# power.net
KiCad netlist of a schematic drawn in Altium Designer
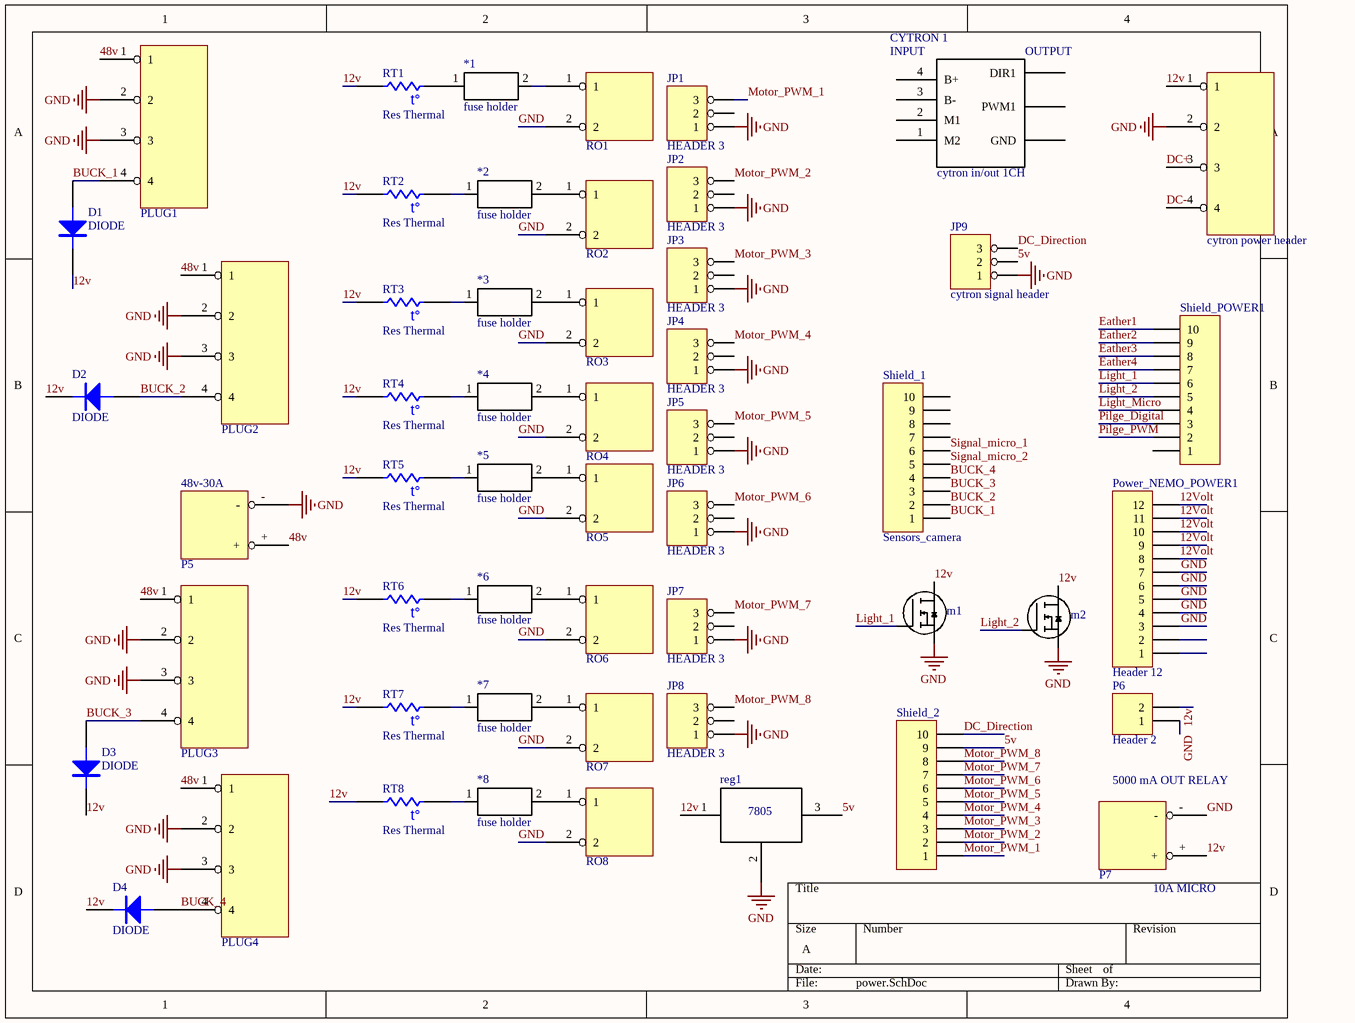
[diagram p0: power.SchDoc]

(export (version "E")
  (design (tool "Eeschema 10.0.6"))
  (components
    (comp (ref "*1")
      (value "fuse holder")
      (footprint "fuse Holder")
      (libsource (lib "RELAY 5V") (part "fuse holder"))
    )
    (comp (ref "*2")
      (value "fuse holder")
      (footprint "fuse Holder")
      (libsource (lib "RELAY 5V") (part "fuse holder"))
    )
    (comp (ref "*3")
      (value "fuse holder")
      (footprint "fuse Holder")
      (libsource (lib "RELAY 5V") (part "fuse holder"))
    )
    (comp (ref "*4")
      (value "fuse holder")
      (footprint "fuse Holder")
      (libsource (lib "RELAY 5V") (part "fuse holder"))
    )
    (comp (ref "*5")
      (value "fuse holder")
      (footprint "fuse Holder")
      (libsource (lib "RELAY 5V") (part "fuse holder"))
    )
    (comp (ref "*6")
      (value "fuse holder")
      (footprint "fuse Holder")
      (libsource (lib "RELAY 5V") (part "fuse holder"))
    )
    (comp (ref "*7")
      (value "fuse holder")
      (footprint "fuse Holder")
      (libsource (lib "RELAY 5V") (part "fuse holder"))
    )
    (comp (ref "*8")
      (value "fuse holder")
      (footprint "fuse Holder")
      (libsource (lib "RELAY 5V") (part "fuse holder"))
    )
    (comp (ref "CYTRON 1")
      (value "cytron in/out 1CH")
      (footprint "cytron in/out 1CH")
      (libsource (lib "RELAY 5V") (part "cytron in/out 1CH"))
    )
    (comp (ref "cytron power header")
      (value "Rossetta 4-pin")
      (footprint "Rossetta 4-pin plugable")
      (fields (field (name "CREATED BY") "NourAldin"))
      (libsource (lib "crocomarine") (part "Rossetta 4-pin"))
    )
    (comp (ref "D1")
      (value "DIODE")
      (footprint "AXIAL0.3")
      (description "Diode")
      (libsource (lib "Final Library") (part "DIODE"))
    )
    (comp (ref "D2")
      (value "DIODE")
      (footprint "AXIAL0.3")
      (description "Diode")
      (libsource (lib "Final Library") (part "DIODE"))
    )
    (comp (ref "D3")
      (value "DIODE")
      (footprint "AXIAL0.3")
      (description "Diode")
      (libsource (lib "Final Library") (part "DIODE"))
    )
    (comp (ref "D4")
      (value "DIODE")
      (footprint "AXIAL0.3")
      (description "Diode")
      (libsource (lib "Final Library") (part "DIODE"))
    )
    (comp (ref "JP1")
      (value "HEADER 3")
      (footprint "SIP3")
      (libsource (lib "Final Library") (part "HEADER 3"))
    )
    (comp (ref "JP2")
      (value "HEADER 3")
      (footprint "SIP3")
      (libsource (lib "Final Library") (part "HEADER 3"))
    )
    (comp (ref "JP3")
      (value "HEADER 3")
      (footprint "SIP3")
      (libsource (lib "Final Library") (part "HEADER 3"))
    )
    (comp (ref "JP4")
      (value "HEADER 3")
      (footprint "SIP3")
      (libsource (lib "Final Library") (part "HEADER 3"))
    )
    (comp (ref "JP5")
      (value "HEADER 3")
      (footprint "SIP3")
      (libsource (lib "Final Library") (part "HEADER 3"))
    )
    (comp (ref "JP6")
      (value "HEADER 3")
      (footprint "SIP3")
      (libsource (lib "Final Library") (part "HEADER 3"))
    )
    (comp (ref "JP7")
      (value "HEADER 3")
      (footprint "SIP3")
      (libsource (lib "Final Library") (part "HEADER 3"))
    )
    (comp (ref "JP8")
      (value "HEADER 3")
      (footprint "SIP3")
      (libsource (lib "Final Library") (part "HEADER 3"))
    )
    (comp (ref "JP9")
      (value "cytron signal header")
      (footprint "SIP3")
      (libsource (lib "Final Library") (part "HEADER 3"))
    )
    (comp (ref "m1")
      (value "MOSFET")
      (footprint "TO252")
      (libsource (lib "sig_lib") (part "MOSFET   AP9997AGH"))
    )
    (comp (ref "m2")
      (value "MOSFET")
      (footprint "TO252")
      (libsource (lib "sig_lib") (part "MOSFET   AP9997AGH"))
    )
    (comp (ref "P5")
      (value "48v-30A")
      (footprint "XT-60")
      (description "XT-60 Connector")
      (libsource (lib "crocomarine (1)") (part "XT-60"))
    )
    (comp (ref "P6")
      (value "Header 2")
      (footprint "HDR1X2")
      (description "Header, 2-Pin")
      (fields (field (name "PUBLISHER") "Altium Limited"))
      (libsource (lib "Miscellaneous Connectors") (part "Header 2"))
    )
    (comp (ref "P7")
      (value "XT-60")
      (footprint "XT-60")
      (description "XT-60 Connector")
      (libsource (lib "crocomarine (1)") (part "XT-60"))
    )
    (comp (ref "PLUG1")
      (value "Rossetta 4-pin")
      (footprint "Rossetta 4-pin plugable")
      (fields (field (name "CREATED BY") "NourAldin"))
      (libsource (lib "crocomarine") (part "Rossetta 4-pin"))
    )
    (comp (ref "PLUG2")
      (value "Rossetta 4-pin")
      (footprint "Rossetta 4-pin plugable")
      (fields (field (name "CREATED BY") "NourAldin"))
      (libsource (lib "crocomarine") (part "Rossetta 4-pin"))
    )
    (comp (ref "PLUG3")
      (value "Rossetta 4-pin")
      (footprint "Rossetta 4-pin plugable")
      (fields (field (name "CREATED BY") "NourAldin"))
      (libsource (lib "crocomarine") (part "Rossetta 4-pin"))
    )
    (comp (ref "PLUG4")
      (value "Rossetta 4-pin")
      (footprint "Rossetta 4-pin plugable")
      (fields (field (name "CREATED BY") "NourAldin"))
      (libsource (lib "crocomarine") (part "Rossetta 4-pin"))
    )
    (comp (ref "Power_NEMO_POWER1")
      (value "Header 12")
      (footprint "HDR1X12")
      (description "Header, 12-Pin")
      (fields (field (name "PUBLISHER") "Altium Limited"))
      (libsource (lib "Miscellaneous Connectors") (part "Header 12"))
    )
    (comp (ref "reg1") (value "7805") (footprint "7805") (libsource (lib "RELAY") (part "7805")))
    (comp (ref "RO1")
      (value "Rossetta")
      (footprint "Rossetta 2-pin")
      (libsource (lib "crocomarine") (part "Rossetta"))
    )
    (comp (ref "RO2")
      (value "Rossetta")
      (footprint "Rossetta 2-pin")
      (libsource (lib "crocomarine") (part "Rossetta"))
    )
    (comp (ref "RO3")
      (value "Rossetta")
      (footprint "Rossetta 2-pin")
      (libsource (lib "crocomarine") (part "Rossetta"))
    )
    (comp (ref "RO4")
      (value "Rossetta")
      (footprint "Rossetta 2-pin")
      (libsource (lib "crocomarine") (part "Rossetta"))
    )
    (comp (ref "RO5")
      (value "Rossetta")
      (footprint "Rossetta 2-pin")
      (libsource (lib "crocomarine") (part "Rossetta"))
    )
    (comp (ref "RO6")
      (value "Rossetta")
      (footprint "Rossetta 2-pin")
      (libsource (lib "crocomarine") (part "Rossetta"))
    )
    (comp (ref "RO7")
      (value "Rossetta")
      (footprint "Rossetta 2-pin")
      (libsource (lib "crocomarine") (part "Rossetta"))
    )
    (comp (ref "RO8")
      (value "Rossetta")
      (footprint "Rossetta 2-pin")
      (libsource (lib "crocomarine") (part "Rossetta"))
    )
    (comp (ref "RT1")
      (value "Res Thermal")
      (footprint "6-0805_N")
      (description "Thermistor")
      (fields (field (name "PUBLISHER") "Altium Limited"))
      (libsource (lib "Miscellaneous Devices") (part "Res Thermal"))
    )
    (comp (ref "RT2")
      (value "Res Thermal")
      (footprint "6-0805_N")
      (description "Thermistor")
      (fields (field (name "PUBLISHER") "Altium Limited"))
      (libsource (lib "Miscellaneous Devices") (part "Res Thermal"))
    )
    (comp (ref "RT3")
      (value "Res Thermal")
      (footprint "6-0805_N")
      (description "Thermistor")
      (fields (field (name "PUBLISHER") "Altium Limited"))
      (libsource (lib "Miscellaneous Devices") (part "Res Thermal"))
    )
    (comp (ref "RT4")
      (value "Res Thermal")
      (footprint "6-0805_N")
      (description "Thermistor")
      (fields (field (name "PUBLISHER") "Altium Limited"))
      (libsource (lib "Miscellaneous Devices") (part "Res Thermal"))
    )
    (comp (ref "RT5")
      (value "Res Thermal")
      (footprint "6-0805_N")
      (description "Thermistor")
      (fields (field (name "PUBLISHER") "Altium Limited"))
      (libsource (lib "Miscellaneous Devices") (part "Res Thermal"))
    )
    (comp (ref "RT6")
      (value "Res Thermal")
      (footprint "6-0805_N")
      (description "Thermistor")
      (fields (field (name "PUBLISHER") "Altium Limited"))
      (libsource (lib "Miscellaneous Devices") (part "Res Thermal"))
    )
    (comp (ref "RT7")
      (value "Res Thermal")
      (footprint "6-0805_N")
      (description "Thermistor")
      (fields (field (name "PUBLISHER") "Altium Limited"))
      (libsource (lib "Miscellaneous Devices") (part "Res Thermal"))
    )
    (comp (ref "RT8")
      (value "Res Thermal")
      (footprint "6-0805_N")
      (description "Thermistor")
      (fields (field (name "PUBLISHER") "Altium Limited"))
      (libsource (lib "Miscellaneous Devices") (part "Res Thermal"))
    )
    (comp (ref "Shield_1")
      (value "Sensors_camera")
      (footprint "HDR1X10")
      (description "Header, 10-Pin")
      (fields (field (name "PUBLISHER") "Altium Limited"))
      (libsource (lib "") (part "Header 10_1"))
    )
    (comp (ref "Shield_2")
      (value "Header 10")
      (footprint "HDR1X10")
      (description "Header, 10-Pin")
      (fields (field (name "PUBLISHER") "Altium Limited"))
      (libsource (lib "") (part "Header 10_1"))
    )
    (comp (ref "Shield_POWER1")
      (value "Header 10")
      (footprint "HDR1X10")
      (description "Header, 10-Pin")
      (fields (field (name "PUBLISHER") "Altium Limited"))
      (libsource (lib "Miscellaneous Connectors") (part "Header 10"))
    )
  )
  (nets
    (net (code "1") (name "/5v") (class "Default")
      (node (ref "JP9") (pin "2") (pinfunction "2_2") (pintype "passive"))
      (node (ref "Shield_2") (pin "9") (pinfunction "9_9") (pintype "passive"))
      (node (ref "reg1") (pin "3") (pinfunction "v_out_3") (pintype "passive"))
    )
    (net (code "2") (name "/12Volt") (class "Default")
      (node (ref "Power_NEMO_POWER1") (pin "10") (pinfunction "10_10") (pintype "passive"))
      (node (ref "Power_NEMO_POWER1") (pin "11") (pinfunction "11_11") (pintype "passive"))
      (node (ref "Power_NEMO_POWER1") (pin "12") (pinfunction "12_12") (pintype "passive"))
      (node (ref "Power_NEMO_POWER1") (pin "8") (pinfunction "8_8") (pintype "passive"))
      (node (ref "Power_NEMO_POWER1") (pin "9") (pinfunction "9_9") (pintype "passive"))
    )
    (net (code "3") (name "/12v") (class "Default")
      (node (ref "D1") (pin "2") (pinfunction "K_2") (pintype "passive"))
      (node (ref "D2") (pin "2") (pinfunction "K_2") (pintype "passive"))
      (node (ref "D3") (pin "2") (pinfunction "K_2") (pintype "passive"))
      (node (ref "D4") (pin "2") (pinfunction "K_2") (pintype "passive"))
      (node (ref "P6") (pin "2") (pinfunction "2_2") (pintype "passive"))
      (node (ref "P7") (pin "+") (pinfunction "+_+") (pintype "passive"))
      (node (ref "RT1") (pin "2") (pinfunction "2_2") (pintype "passive"))
      (node (ref "RT2") (pin "2") (pinfunction "2_2") (pintype "passive"))
      (node (ref "RT3") (pin "2") (pinfunction "2_2") (pintype "passive"))
      (node (ref "RT4") (pin "2") (pinfunction "2_2") (pintype "passive"))
      (node (ref "RT5") (pin "2") (pinfunction "2_2") (pintype "passive"))
      (node (ref "RT6") (pin "2") (pinfunction "2_2") (pintype "passive"))
      (node (ref "RT7") (pin "2") (pinfunction "2_2") (pintype "passive"))
      (node (ref "RT8") (pin "2") (pinfunction "2_2") (pintype "passive"))
      (node (ref "cytron power header") (pin "1") (pinfunction "1_1") (pintype "passive"))
      (node (ref "m1") (pin "D") (pinfunction "D_D") (pintype "passive"))
      (node (ref "m2") (pin "D") (pinfunction "D_D") (pintype "passive"))
      (node (ref "reg1") (pin "1") (pinfunction "v_in_1") (pintype "passive"))
    )
    (net (code "4") (name "/48v") (class "Default")
      (node (ref "P5") (pin "+") (pinfunction "+_+") (pintype "passive"))
      (node (ref "PLUG1") (pin "1") (pinfunction "1_1") (pintype "passive"))
      (node (ref "PLUG2") (pin "1") (pinfunction "1_1") (pintype "passive"))
      (node (ref "PLUG3") (pin "1") (pinfunction "1_1") (pintype "passive"))
      (node (ref "PLUG4") (pin "1") (pinfunction "1_1") (pintype "passive"))
    )
    (net (code "5") (name "/BUCK_1") (class "Default")
      (node (ref "D1") (pin "1") (pinfunction "A_1") (pintype "passive"))
      (node (ref "PLUG1") (pin "4") (pinfunction "4_4") (pintype "passive"))
      (node (ref "Shield_1") (pin "1") (pinfunction "1_1") (pintype "passive"))
    )
    (net (code "6") (name "/BUCK_2") (class "Default")
      (node (ref "D2") (pin "1") (pinfunction "A_1") (pintype "passive"))
      (node (ref "PLUG2") (pin "4") (pinfunction "4_4") (pintype "passive"))
      (node (ref "Shield_1") (pin "2") (pinfunction "2_2") (pintype "passive"))
    )
    (net (code "7") (name "/BUCK_3") (class "Default")
      (node (ref "D3") (pin "1") (pinfunction "A_1") (pintype "passive"))
      (node (ref "PLUG3") (pin "4") (pinfunction "4_4") (pintype "passive"))
      (node (ref "Shield_1") (pin "3") (pinfunction "3_3") (pintype "passive"))
    )
    (net (code "8") (name "/BUCK_4") (class "Default")
      (node (ref "D4") (pin "1") (pinfunction "A_1") (pintype "passive"))
      (node (ref "PLUG4") (pin "4") (pinfunction "4_4") (pintype "passive"))
      (node (ref "Shield_1") (pin "4") (pinfunction "4_4") (pintype "passive"))
    )
    (net (code "9") (name "/DC+") (class "Default")
      (node (ref "cytron power header") (pin "3") (pinfunction "3_3") (pintype "passive"))
    )
    (net (code "10") (name "/DC-") (class "Default")
      (node (ref "cytron power header") (pin "4") (pinfunction "4_4") (pintype "passive"))
    )
    (net (code "11") (name "/DC_Direction") (class "Default")
      (node (ref "JP9") (pin "3") (pinfunction "3_3") (pintype "passive"))
      (node (ref "Shield_2") (pin "10") (pinfunction "10_10") (pintype "passive"))
    )
    (net (code "12") (name "/Eather1") (class "Default")
      (node (ref "Shield_POWER1") (pin "10") (pinfunction "10_10") (pintype "passive"))
    )
    (net (code "13") (name "/Eather2") (class "Default")
      (node (ref "Shield_POWER1") (pin "9") (pinfunction "9_9") (pintype "passive"))
    )
    (net (code "14") (name "/Eather3") (class "Default")
      (node (ref "Shield_POWER1") (pin "8") (pinfunction "8_8") (pintype "passive"))
    )
    (net (code "15") (name "/Eather4") (class "Default")
      (node (ref "Shield_POWER1") (pin "7") (pinfunction "7_7") (pintype "passive"))
    )
    (net (code "16") (name "/Light_1") (class "Default")
      (node (ref "Shield_POWER1") (pin "6") (pinfunction "6_6") (pintype "passive"))
      (node (ref "m1") (pin "G") (pinfunction "G_G") (pintype "passive"))
    )
    (net (code "17") (name "/Light_2") (class "Default")
      (node (ref "Shield_POWER1") (pin "5") (pinfunction "5_5") (pintype "passive"))
      (node (ref "m2") (pin "G") (pinfunction "G_G") (pintype "passive"))
    )
    (net (code "18") (name "/Light_Micro") (class "Default")
      (node (ref "Shield_POWER1") (pin "4") (pinfunction "4_4") (pintype "passive"))
    )
    (net (code "19") (name "/Motor_PWM_1") (class "Default")
      (node (ref "JP1") (pin "3") (pinfunction "3_3") (pintype "passive"))
      (node (ref "Shield_2") (pin "1") (pinfunction "1_1") (pintype "passive"))
    )
    (net (code "20") (name "/Motor_PWM_2") (class "Default")
      (node (ref "JP2") (pin "3") (pinfunction "3_3") (pintype "passive"))
      (node (ref "Shield_2") (pin "2") (pinfunction "2_2") (pintype "passive"))
    )
    (net (code "21") (name "/Motor_PWM_3") (class "Default")
      (node (ref "JP3") (pin "3") (pinfunction "3_3") (pintype "passive"))
      (node (ref "Shield_2") (pin "3") (pinfunction "3_3") (pintype "passive"))
    )
    (net (code "22") (name "/Motor_PWM_4") (class "Default")
      (node (ref "JP4") (pin "3") (pinfunction "3_3") (pintype "passive"))
      (node (ref "Shield_2") (pin "4") (pinfunction "4_4") (pintype "passive"))
    )
    (net (code "23") (name "/Motor_PWM_5") (class "Default")
      (node (ref "JP5") (pin "3") (pinfunction "3_3") (pintype "passive"))
      (node (ref "Shield_2") (pin "5") (pinfunction "5_5") (pintype "passive"))
    )
    (net (code "24") (name "/Motor_PWM_6") (class "Default")
      (node (ref "JP6") (pin "3") (pinfunction "3_3") (pintype "passive"))
      (node (ref "Shield_2") (pin "6") (pinfunction "6_6") (pintype "passive"))
    )
    (net (code "25") (name "/Motor_PWM_7") (class "Default")
      (node (ref "JP7") (pin "3") (pinfunction "3_3") (pintype "passive"))
      (node (ref "Shield_2") (pin "7") (pinfunction "7_7") (pintype "passive"))
    )
    (net (code "26") (name "/Motor_PWM_8") (class "Default")
      (node (ref "JP8") (pin "3") (pinfunction "3_3") (pintype "passive"))
      (node (ref "Shield_2") (pin "8") (pinfunction "8_8") (pintype "passive"))
    )
    (net (code "27") (name "/Pilge_Digital") (class "Default")
      (node (ref "Shield_POWER1") (pin "3") (pinfunction "3_3") (pintype "passive"))
    )
    (net (code "28") (name "/Pilge_PWM") (class "Default")
      (node (ref "Shield_POWER1") (pin "2") (pinfunction "2_2") (pintype "passive"))
    )
    (net (code "29") (name "/Signal_micro_1") (class "Default")
      (node (ref "Shield_1") (pin "6") (pinfunction "6_6") (pintype "passive"))
    )
    (net (code "30") (name "/Signal_micro_2") (class "Default")
      (node (ref "Shield_1") (pin "5") (pinfunction "5_5") (pintype "passive"))
    )
    (net (code "31") (name "GND") (class "Default")
      (node (ref "JP1") (pin "1") (pinfunction "1_1") (pintype "passive"))
      (node (ref "JP2") (pin "1") (pinfunction "1_1") (pintype "passive"))
      (node (ref "JP3") (pin "1") (pinfunction "1_1") (pintype "passive"))
      (node (ref "JP4") (pin "1") (pinfunction "1_1") (pintype "passive"))
      (node (ref "JP5") (pin "1") (pinfunction "1_1") (pintype "passive"))
      (node (ref "JP6") (pin "1") (pinfunction "1_1") (pintype "passive"))
      (node (ref "JP7") (pin "1") (pinfunction "1_1") (pintype "passive"))
      (node (ref "JP8") (pin "1") (pinfunction "1_1") (pintype "passive"))
      (node (ref "JP9") (pin "1") (pinfunction "1_1") (pintype "passive"))
      (node (ref "P5") (pin "-") (pinfunction "-_-") (pintype "passive"))
      (node (ref "P6") (pin "1") (pinfunction "1_1") (pintype "passive"))
      (node (ref "P7") (pin "-") (pinfunction "-_-") (pintype "passive"))
      (node (ref "PLUG1") (pin "2") (pinfunction "2_2") (pintype "passive"))
      (node (ref "PLUG1") (pin "3") (pinfunction "3_3") (pintype "passive"))
      (node (ref "PLUG2") (pin "2") (pinfunction "2_2") (pintype "passive"))
      (node (ref "PLUG2") (pin "3") (pinfunction "3_3") (pintype "passive"))
      (node (ref "PLUG3") (pin "2") (pinfunction "2_2") (pintype "passive"))
      (node (ref "PLUG3") (pin "3") (pinfunction "3_3") (pintype "passive"))
      (node (ref "PLUG4") (pin "2") (pinfunction "2_2") (pintype "passive"))
      (node (ref "PLUG4") (pin "3") (pinfunction "3_3") (pintype "passive"))
      (node (ref "Power_NEMO_POWER1") (pin "3") (pinfunction "3_3") (pintype "passive"))
      (node (ref "Power_NEMO_POWER1") (pin "4") (pinfunction "4_4") (pintype "passive"))
      (node (ref "Power_NEMO_POWER1") (pin "5") (pinfunction "5_5") (pintype "passive"))
      (node (ref "Power_NEMO_POWER1") (pin "6") (pinfunction "6_6") (pintype "passive"))
      (node (ref "Power_NEMO_POWER1") (pin "7") (pinfunction "7_7") (pintype "passive"))
      (node (ref "RO1") (pin "2") (pinfunction "2_2") (pintype "passive"))
      (node (ref "RO2") (pin "2") (pinfunction "2_2") (pintype "passive"))
      (node (ref "RO3") (pin "2") (pinfunction "2_2") (pintype "passive"))
      (node (ref "RO4") (pin "2") (pinfunction "2_2") (pintype "passive"))
      (node (ref "RO5") (pin "2") (pinfunction "2_2") (pintype "passive"))
      (node (ref "RO6") (pin "2") (pinfunction "2_2") (pintype "passive"))
      (node (ref "RO7") (pin "2") (pinfunction "2_2") (pintype "passive"))
      (node (ref "RO8") (pin "2") (pinfunction "2_2") (pintype "passive"))
      (node (ref "cytron power header") (pin "2") (pinfunction "2_2") (pintype "passive"))
      (node (ref "m1") (pin "S") (pinfunction "S_S") (pintype "passive"))
      (node (ref "m2") (pin "S") (pinfunction "S_S") (pintype "passive"))
      (node (ref "reg1") (pin "2") (pinfunction "gnd_2") (pintype "passive"))
    )
    (net (code "32") (name "Net-(*1-Pad1)") (class "Default")
      (node (ref "*1") (pin "1") (pinfunction "1_1") (pintype "passive"))
      (node (ref "RT1") (pin "1") (pinfunction "1_1") (pintype "passive"))
    )
    (net (code "33") (name "Net-(*1-Pad2)") (class "Default")
      (node (ref "*1") (pin "2") (pinfunction "2_2") (pintype "passive"))
      (node (ref "RO1") (pin "1") (pinfunction "1_1") (pintype "passive"))
    )
    (net (code "34") (name "Net-(*2-Pad1)") (class "Default")
      (node (ref "*2") (pin "1") (pinfunction "1_1") (pintype "passive"))
      (node (ref "RT2") (pin "1") (pinfunction "1_1") (pintype "passive"))
    )
    (net (code "35") (name "Net-(*2-Pad2)") (class "Default")
      (node (ref "*2") (pin "2") (pinfunction "2_2") (pintype "passive"))
      (node (ref "RO2") (pin "1") (pinfunction "1_1") (pintype "passive"))
    )
    (net (code "36") (name "Net-(*3-Pad1)") (class "Default")
      (node (ref "*3") (pin "1") (pinfunction "1_1") (pintype "passive"))
      (node (ref "RT3") (pin "1") (pinfunction "1_1") (pintype "passive"))
    )
    (net (code "37") (name "Net-(*3-Pad2)") (class "Default")
      (node (ref "*3") (pin "2") (pinfunction "2_2") (pintype "passive"))
      (node (ref "RO3") (pin "1") (pinfunction "1_1") (pintype "passive"))
    )
    (net (code "38") (name "Net-(*4-Pad1)") (class "Default")
      (node (ref "*4") (pin "1") (pinfunction "1_1") (pintype "passive"))
      (node (ref "RT4") (pin "1") (pinfunction "1_1") (pintype "passive"))
    )
    (net (code "39") (name "Net-(*4-Pad2)") (class "Default")
      (node (ref "*4") (pin "2") (pinfunction "2_2") (pintype "passive"))
      (node (ref "RO4") (pin "1") (pinfunction "1_1") (pintype "passive"))
    )
    (net (code "40") (name "Net-(*5-Pad1)") (class "Default")
      (node (ref "*5") (pin "1") (pinfunction "1_1") (pintype "passive"))
      (node (ref "RT5") (pin "1") (pinfunction "1_1") (pintype "passive"))
    )
    (net (code "41") (name "Net-(*5-Pad2)") (class "Default")
      (node (ref "*5") (pin "2") (pinfunction "2_2") (pintype "passive"))
      (node (ref "RO5") (pin "1") (pinfunction "1_1") (pintype "passive"))
    )
    (net (code "42") (name "Net-(*6-Pad1)") (class "Default")
      (node (ref "*6") (pin "1") (pinfunction "1_1") (pintype "passive"))
      (node (ref "RT6") (pin "1") (pinfunction "1_1") (pintype "passive"))
    )
    (net (code "43") (name "Net-(*6-Pad2)") (class "Default")
      (node (ref "*6") (pin "2") (pinfunction "2_2") (pintype "passive"))
      (node (ref "RO6") (pin "1") (pinfunction "1_1") (pintype "passive"))
    )
    (net (code "44") (name "Net-(*7-Pad1)") (class "Default")
      (node (ref "*7") (pin "1") (pinfunction "1_1") (pintype "passive"))
      (node (ref "RT7") (pin "1") (pinfunction "1_1") (pintype "passive"))
    )
    (net (code "45") (name "Net-(*7-Pad2)") (class "Default")
      (node (ref "*7") (pin "2") (pinfunction "2_2") (pintype "passive"))
      (node (ref "RO7") (pin "1") (pinfunction "1_1") (pintype "passive"))
    )
    (net (code "46") (name "Net-(*8-Pad1)") (class "Default")
      (node (ref "*8") (pin "1") (pinfunction "1_1") (pintype "passive"))
      (node (ref "RT8") (pin "1") (pinfunction "1_1") (pintype "passive"))
    )
    (net (code "47") (name "Net-(*8-Pad2)") (class "Default")
      (node (ref "*8") (pin "2") (pinfunction "2_2") (pintype "passive"))
      (node (ref "RO8") (pin "1") (pinfunction "1_1") (pintype "passive"))
    )
    (net (code "48") (name "unconnected-(CYTRON 1-B+-Pad4)") (class "Default")
      (node (ref "CYTRON 1") (pin "4") (pinfunction "B+_4") (pintype "passive"))
    )
    (net (code "49") (name "unconnected-(CYTRON 1-B--Pad3)") (class "Default")
      (node (ref "CYTRON 1") (pin "3") (pinfunction "B-_3") (pintype "passive"))
    )
    (net (code "50") (name "unconnected-(CYTRON 1-DIR1-Pad5)") (class "Default")
      (node (ref "CYTRON 1") (pin "5") (pinfunction "DIR1_5") (pintype "passive"))
    )
    (net (code "51") (name "unconnected-(CYTRON 1-GND-Pad7)") (class "Default")
      (node (ref "CYTRON 1") (pin "7") (pinfunction "GND_7") (pintype "passive"))
    )
    (net (code "52") (name "unconnected-(CYTRON 1-M1-Pad2)") (class "Default")
      (node (ref "CYTRON 1") (pin "2") (pinfunction "M1_2") (pintype "passive"))
    )
    (net (code "53") (name "unconnected-(CYTRON 1-M2-Pad1)") (class "Default")
      (node (ref "CYTRON 1") (pin "1") (pinfunction "M2_1") (pintype "passive"))
    )
    (net (code "54") (name "unconnected-(CYTRON 1-PWM1-Pad6)") (class "Default")
      (node (ref "CYTRON 1") (pin "6") (pinfunction "PWM1_6") (pintype "passive"))
    )
    (net (code "55") (name "unconnected-(JP1-Pad2)") (class "Default")
      (node (ref "JP1") (pin "2") (pinfunction "2_2") (pintype "passive"))
    )
    (net (code "56") (name "unconnected-(JP2-Pad2)") (class "Default")
      (node (ref "JP2") (pin "2") (pinfunction "2_2") (pintype "passive"))
    )
    (net (code "57") (name "unconnected-(JP3-Pad2)") (class "Default")
      (node (ref "JP3") (pin "2") (pinfunction "2_2") (pintype "passive"))
    )
    (net (code "58") (name "unconnected-(JP4-Pad2)") (class "Default")
      (node (ref "JP4") (pin "2") (pinfunction "2_2") (pintype "passive"))
    )
    (net (code "59") (name "unconnected-(JP5-Pad2)") (class "Default")
      (node (ref "JP5") (pin "2") (pinfunction "2_2") (pintype "passive"))
    )
    (net (code "60") (name "unconnected-(JP6-Pad2)") (class "Default")
      (node (ref "JP6") (pin "2") (pinfunction "2_2") (pintype "passive"))
    )
    (net (code "61") (name "unconnected-(JP7-Pad2)") (class "Default")
      (node (ref "JP7") (pin "2") (pinfunction "2_2") (pintype "passive"))
    )
    (net (code "62") (name "unconnected-(JP8-Pad2)") (class "Default")
      (node (ref "JP8") (pin "2") (pinfunction "2_2") (pintype "passive"))
    )
    (net (code "63") (name "unconnected-(Power_NEMO_POWER1-Pad1)") (class "Default")
      (node (ref "Power_NEMO_POWER1") (pin "1") (pinfunction "1_1") (pintype "passive"))
    )
    (net (code "64") (name "unconnected-(Power_NEMO_POWER1-Pad2)") (class "Default")
      (node (ref "Power_NEMO_POWER1") (pin "2") (pinfunction "2_2") (pintype "passive"))
    )
    (net (code "65") (name "unconnected-(Shield_1-Pad7)") (class "Default")
      (node (ref "Shield_1") (pin "7") (pinfunction "7_7") (pintype "passive"))
    )
    (net (code "66") (name "unconnected-(Shield_1-Pad8)") (class "Default")
      (node (ref "Shield_1") (pin "8") (pinfunction "8_8") (pintype "passive"))
    )
    (net (code "67") (name "unconnected-(Shield_1-Pad9)") (class "Default")
      (node (ref "Shield_1") (pin "9") (pinfunction "9_9") (pintype "passive"))
    )
    (net (code "68") (name "unconnected-(Shield_1-Pad10)") (class "Default")
      (node (ref "Shield_1") (pin "10") (pinfunction "10_10") (pintype "passive"))
    )
    (net (code "69") (name "unconnected-(Shield_POWER1-Pad1)") (class "Default")
      (node (ref "Shield_POWER1") (pin "1") (pinfunction "1_1") (pintype "passive"))
    )
  )
)
